# SCH.net
KiCad netlist of a schematic drawn in EasyEDA
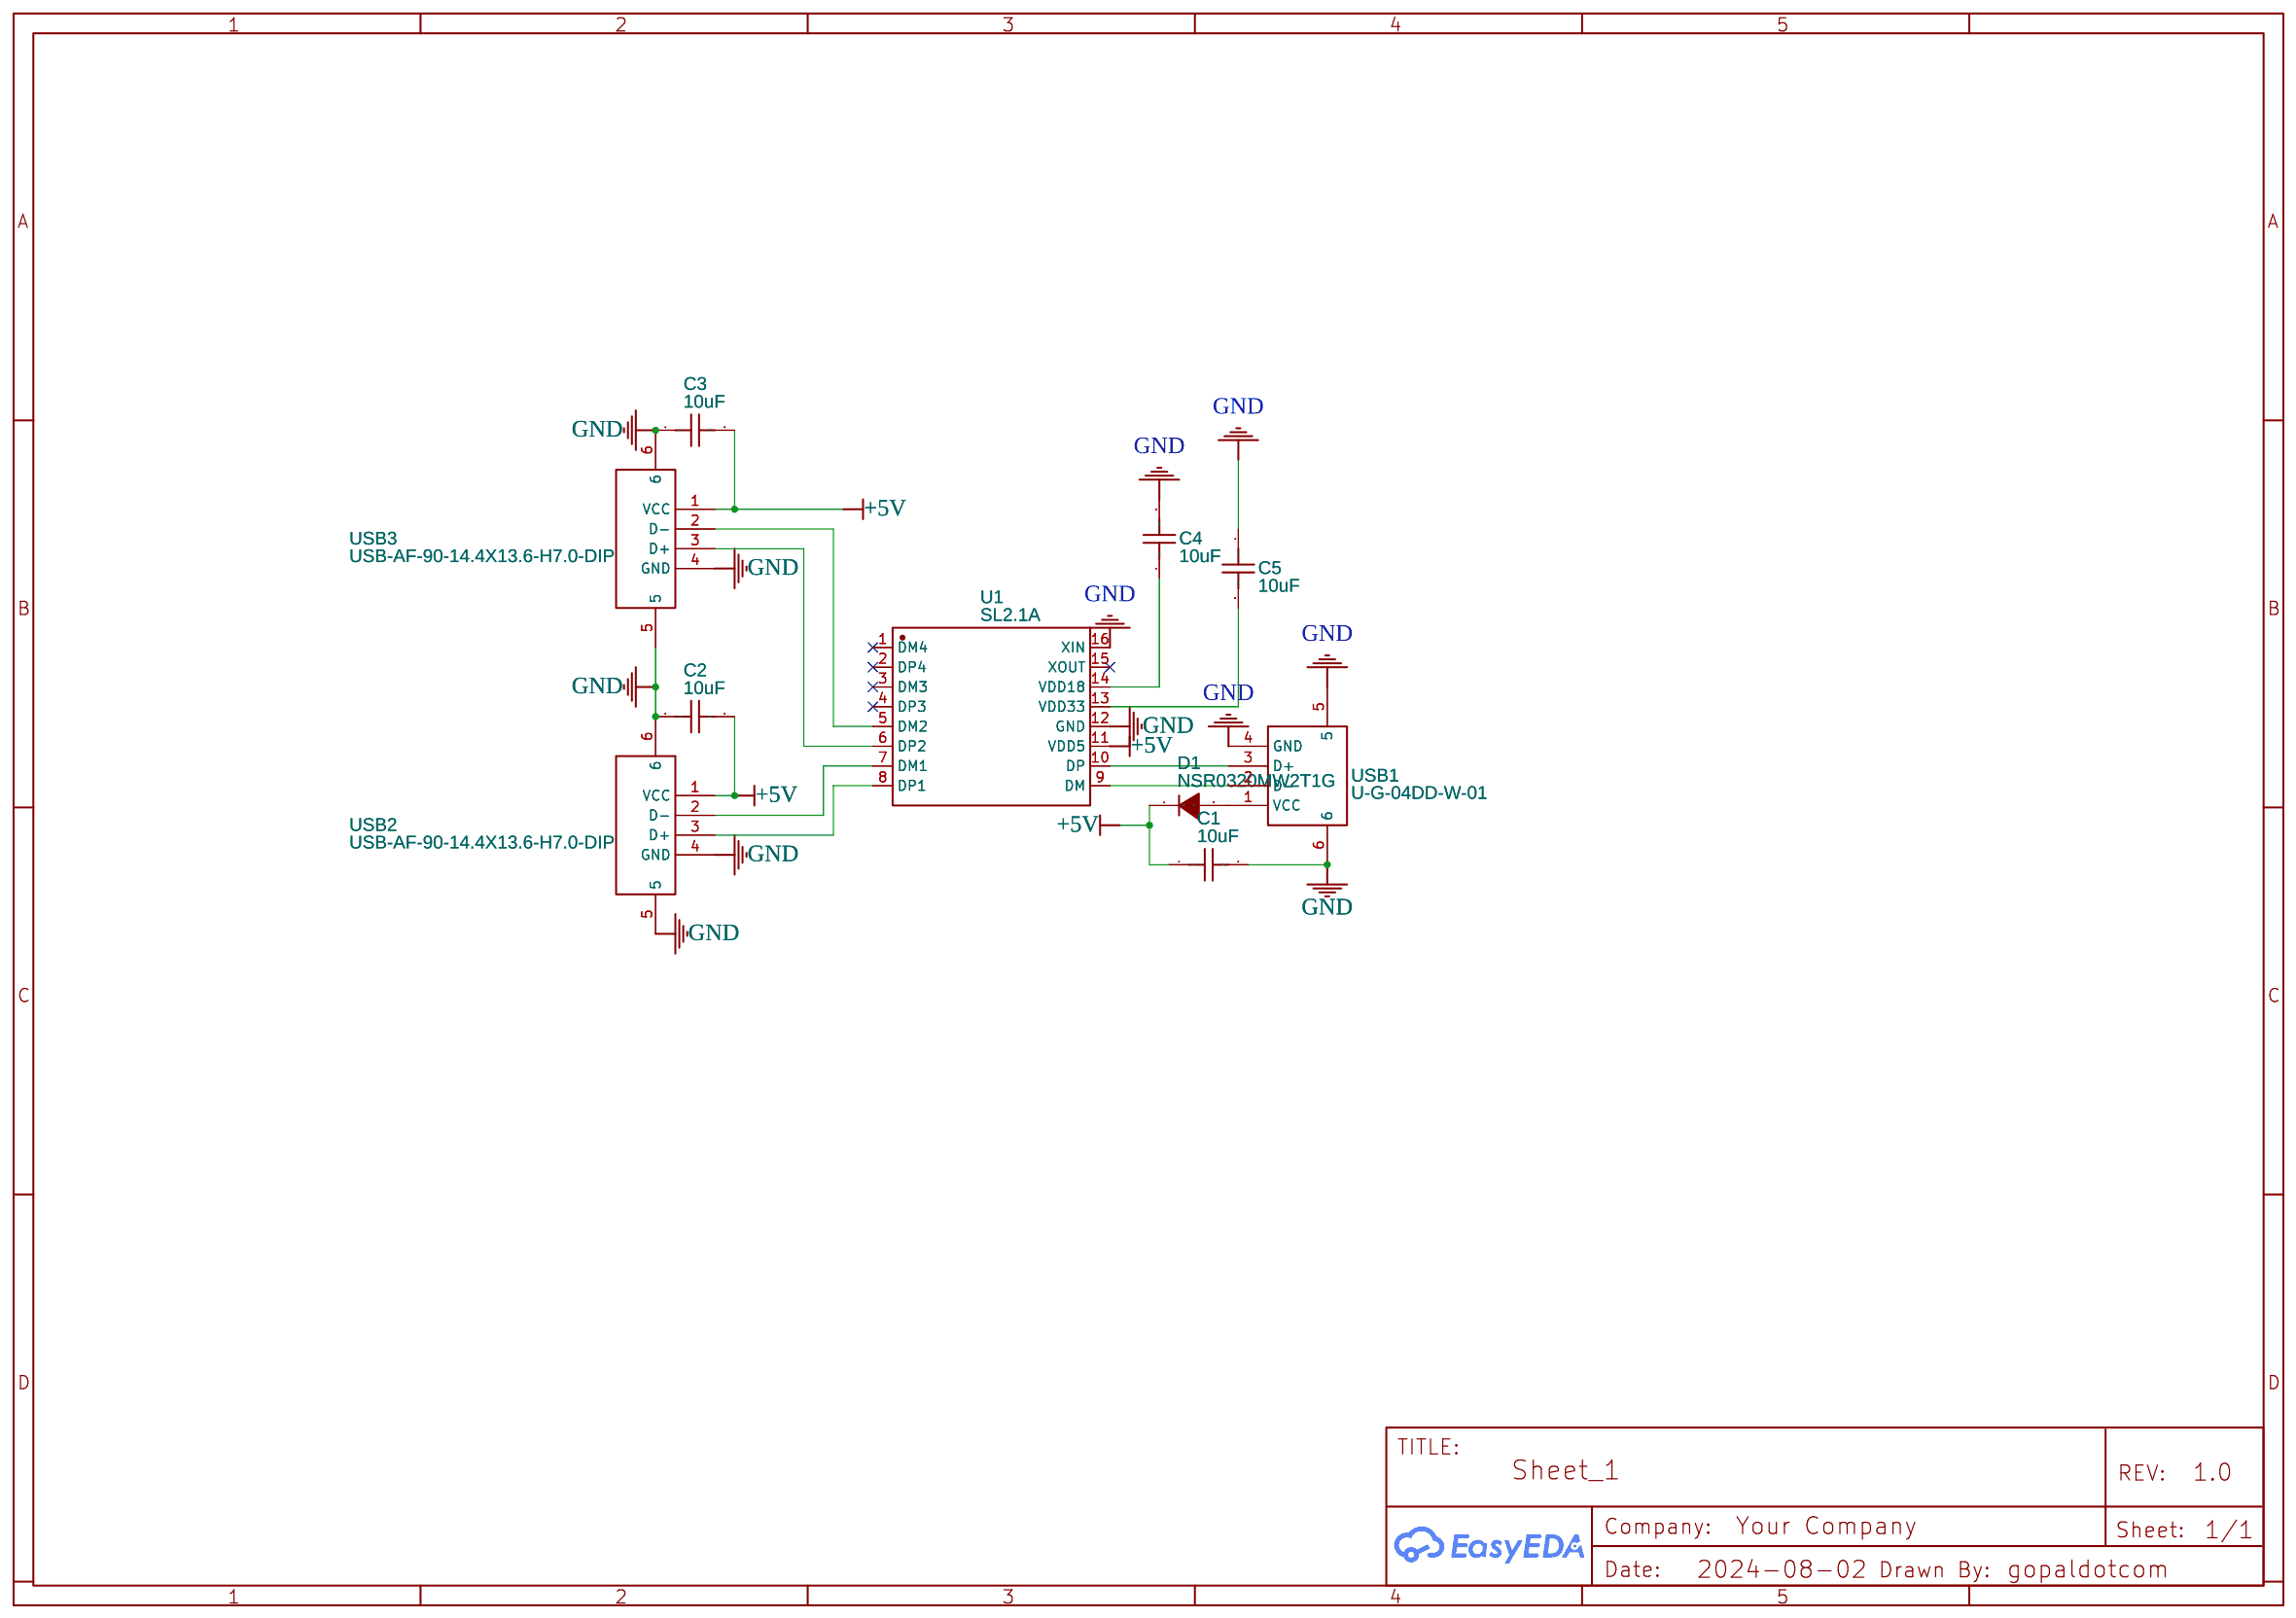
[diagram p0: schematic sheet]

(export (version "E")
  (design (tool "Eeschema 10.0.6"))
  (components
    (comp (ref "C1")
      (value "10uF")
      (fields
        (field (name "Manufacturer Part") "CL10A106KP8NNNC")
        (field (name "Manufacturer") "SAMSUNG(三星)")
      )
      (libsource (lib "") (part "CL10A106KP8NNNC"))
    )
    (comp (ref "C2")
      (value "10uF")
      (fields
        (field (name "Manufacturer Part") "CL10A106KP8NNNC")
        (field (name "Manufacturer") "SAMSUNG(三星)")
      )
      (libsource (lib "") (part "CL10A106KP8NNNC"))
    )
    (comp (ref "C3")
      (value "10uF")
      (fields
        (field (name "Manufacturer Part") "CL10A106KP8NNNC")
        (field (name "Manufacturer") "SAMSUNG(三星)")
      )
      (libsource (lib "") (part "CL10A106KP8NNNC"))
    )
    (comp (ref "C4")
      (value "10uF")
      (fields
        (field (name "Manufacturer Part") "CL10A106KP8NNNC")
        (field (name "Manufacturer") "SAMSUNG(三星)")
      )
      (libsource (lib "") (part "CL10A106KP8NNNC_1"))
    )
    (comp (ref "C5")
      (value "10uF")
      (fields
        (field (name "Manufacturer Part") "CL10A106KP8NNNC")
        (field (name "Manufacturer") "SAMSUNG(三星)")
      )
      (libsource (lib "") (part "CL10A106KP8NNNC_2"))
    )
    (comp (ref "D1")
      (value "NSR0320MW2T1G")
      (fields (field (name "Manufacturer") "onsemi(安森美)"))
      (libsource (lib "") (part "NSR0320MW2T1G"))
    )
    (comp (ref "U1")
      (value "SL2.1A")
      (fields (field (name "Manufacturer") "CoreChips(和芯润德)"))
      (libsource (lib "") (part "SL2.1A"))
    )
    (comp (ref "USB1")
      (value "U-G-04DD-W-01")
      (fields (field (name "Manufacturer Part") "U-G-O4DD-W-1") (field (name "Manufacturer") "韩国韩荣"))
      (libsource (lib "") (part "U-G-04DD-W-01"))
    )
    (comp (ref "USB2")
      (value "USB-AF-90-14.4X13.6-H7.0-DIP")
      (fields (field (name "Manufacturer Part") "903-131A1011D10100") (field (name "Manufacturer") "精拓金"))
      (libsource (lib "") (part "USB-AF-90-14.4X13.6-H7.0-DIP"))
    )
    (comp (ref "USB3")
      (value "USB-AF-90-14.4X13.6-H7.0-DIP")
      (fields (field (name "Manufacturer Part") "903-131A1011D10100") (field (name "Manufacturer") "精拓金"))
      (libsource (lib "") (part "USB-AF-90-14.4X13.6-H7.0-DIP"))
    )
  )
  (nets
    (net (code "1") (name "+5V") (class "Default")
      (node (ref "C1") (pin "1") (pinfunction "1_1") (pintype "unspecified"))
      (node (ref "C2") (pin "2") (pinfunction "2_2") (pintype "unspecified"))
      (node (ref "C3") (pin "2") (pinfunction "2_2") (pintype "unspecified"))
      (node (ref "D1") (pin "1") (pinfunction "C_1") (pintype "unspecified"))
      (node (ref "U1") (pin "11") (pinfunction "VDD5_11") (pintype "unspecified"))
      (node (ref "USB2") (pin "1") (pinfunction "VCC_1") (pintype "unspecified"))
      (node (ref "USB3") (pin "1") (pinfunction "VCC_1") (pintype "unspecified"))
    )
    (net (code "2") (name "GND") (class "Default")
      (node (ref "C1") (pin "2") (pinfunction "2_2") (pintype "unspecified"))
      (node (ref "C2") (pin "1") (pinfunction "1_1") (pintype "unspecified"))
      (node (ref "C3") (pin "1") (pinfunction "1_1") (pintype "unspecified"))
      (node (ref "C4") (pin "2") (pinfunction "2_2") (pintype "unspecified"))
      (node (ref "C5") (pin "1") (pinfunction "1_1") (pintype "unspecified"))
      (node (ref "U1") (pin "12") (pinfunction "GND_12") (pintype "unspecified"))
      (node (ref "U1") (pin "16") (pinfunction "XIN_16") (pintype "unspecified"))
      (node (ref "USB1") (pin "4") (pinfunction "GND_4") (pintype "unspecified"))
      (node (ref "USB1") (pin "5") (pinfunction "5_5") (pintype "unspecified"))
      (node (ref "USB1") (pin "6") (pinfunction "6_6") (pintype "unspecified"))
      (node (ref "USB2") (pin "4") (pinfunction "GND_4") (pintype "unspecified"))
      (node (ref "USB2") (pin "5") (pinfunction "5_5") (pintype "unspecified"))
      (node (ref "USB2") (pin "6") (pinfunction "6_6") (pintype "unspecified"))
      (node (ref "USB3") (pin "4") (pinfunction "GND_4") (pintype "unspecified"))
      (node (ref "USB3") (pin "5") (pinfunction "5_5") (pintype "unspecified"))
      (node (ref "USB3") (pin "6") (pinfunction "6_6") (pintype "unspecified"))
    )
    (net (code "3") (name "Net-(D1-A)") (class "Default")
      (node (ref "D1") (pin "2") (pinfunction "A_2") (pintype "unspecified"))
      (node (ref "USB1") (pin "1") (pinfunction "VCC_1") (pintype "unspecified"))
    )
    (net (code "4") (name "Net-(U1-DM)") (class "Default")
      (node (ref "U1") (pin "9") (pinfunction "DM_9") (pintype "unspecified"))
      (node (ref "USB1") (pin "2") (pinfunction "D-_2") (pintype "unspecified"))
    )
    (net (code "5") (name "Net-(U1-DM1)") (class "Default")
      (node (ref "U1") (pin "7") (pinfunction "DM1_7") (pintype "unspecified"))
      (node (ref "USB2") (pin "2") (pinfunction "D-_2") (pintype "unspecified"))
    )
    (net (code "6") (name "Net-(U1-DM2)") (class "Default")
      (node (ref "U1") (pin "5") (pinfunction "DM2_5") (pintype "unspecified"))
      (node (ref "USB3") (pin "2") (pinfunction "D-_2") (pintype "unspecified"))
    )
    (net (code "7") (name "Net-(U1-DP)") (class "Default")
      (node (ref "U1") (pin "10") (pinfunction "DP_10") (pintype "unspecified"))
      (node (ref "USB1") (pin "3") (pinfunction "D+_3") (pintype "unspecified"))
    )
    (net (code "8") (name "Net-(U1-DP1)") (class "Default")
      (node (ref "U1") (pin "8") (pinfunction "DP1_8") (pintype "unspecified"))
      (node (ref "USB2") (pin "3") (pinfunction "D+_3") (pintype "unspecified"))
    )
    (net (code "9") (name "Net-(U1-DP2)") (class "Default")
      (node (ref "U1") (pin "6") (pinfunction "DP2_6") (pintype "unspecified"))
      (node (ref "USB3") (pin "3") (pinfunction "D+_3") (pintype "unspecified"))
    )
    (net (code "10") (name "Net-(U1-VDD18)") (class "Default")
      (node (ref "C4") (pin "1") (pinfunction "1_1") (pintype "unspecified"))
      (node (ref "U1") (pin "14") (pinfunction "VDD18_14") (pintype "unspecified"))
    )
    (net (code "11") (name "Net-(U1-VDD33)") (class "Default")
      (node (ref "C5") (pin "2") (pinfunction "2_2") (pintype "unspecified"))
      (node (ref "U1") (pin "13") (pinfunction "VDD33_13") (pintype "unspecified"))
    )
    (net (code "12") (name "unconnected-(U1-DM3-Pad3)") (class "Default")
      (node (ref "U1") (pin "3") (pinfunction "DM3_3") (pintype "unspecified+no_connect"))
    )
    (net (code "13") (name "unconnected-(U1-DM4-Pad1)") (class "Default")
      (node (ref "U1") (pin "1") (pinfunction "DM4_1") (pintype "unspecified+no_connect"))
    )
    (net (code "14") (name "unconnected-(U1-DP3-Pad4)") (class "Default")
      (node (ref "U1") (pin "4") (pinfunction "DP3_4") (pintype "unspecified+no_connect"))
    )
    (net (code "15") (name "unconnected-(U1-DP4-Pad2)") (class "Default")
      (node (ref "U1") (pin "2") (pinfunction "DP4_2") (pintype "unspecified+no_connect"))
    )
    (net (code "16") (name "unconnected-(U1-XOUT-Pad15)") (class "Default")
      (node (ref "U1") (pin "15") (pinfunction "XOUT_15") (pintype "unspecified+no_connect"))
    )
  )
)
